# Schematic.net
KiCad netlist of a schematic drawn in Altium Designer
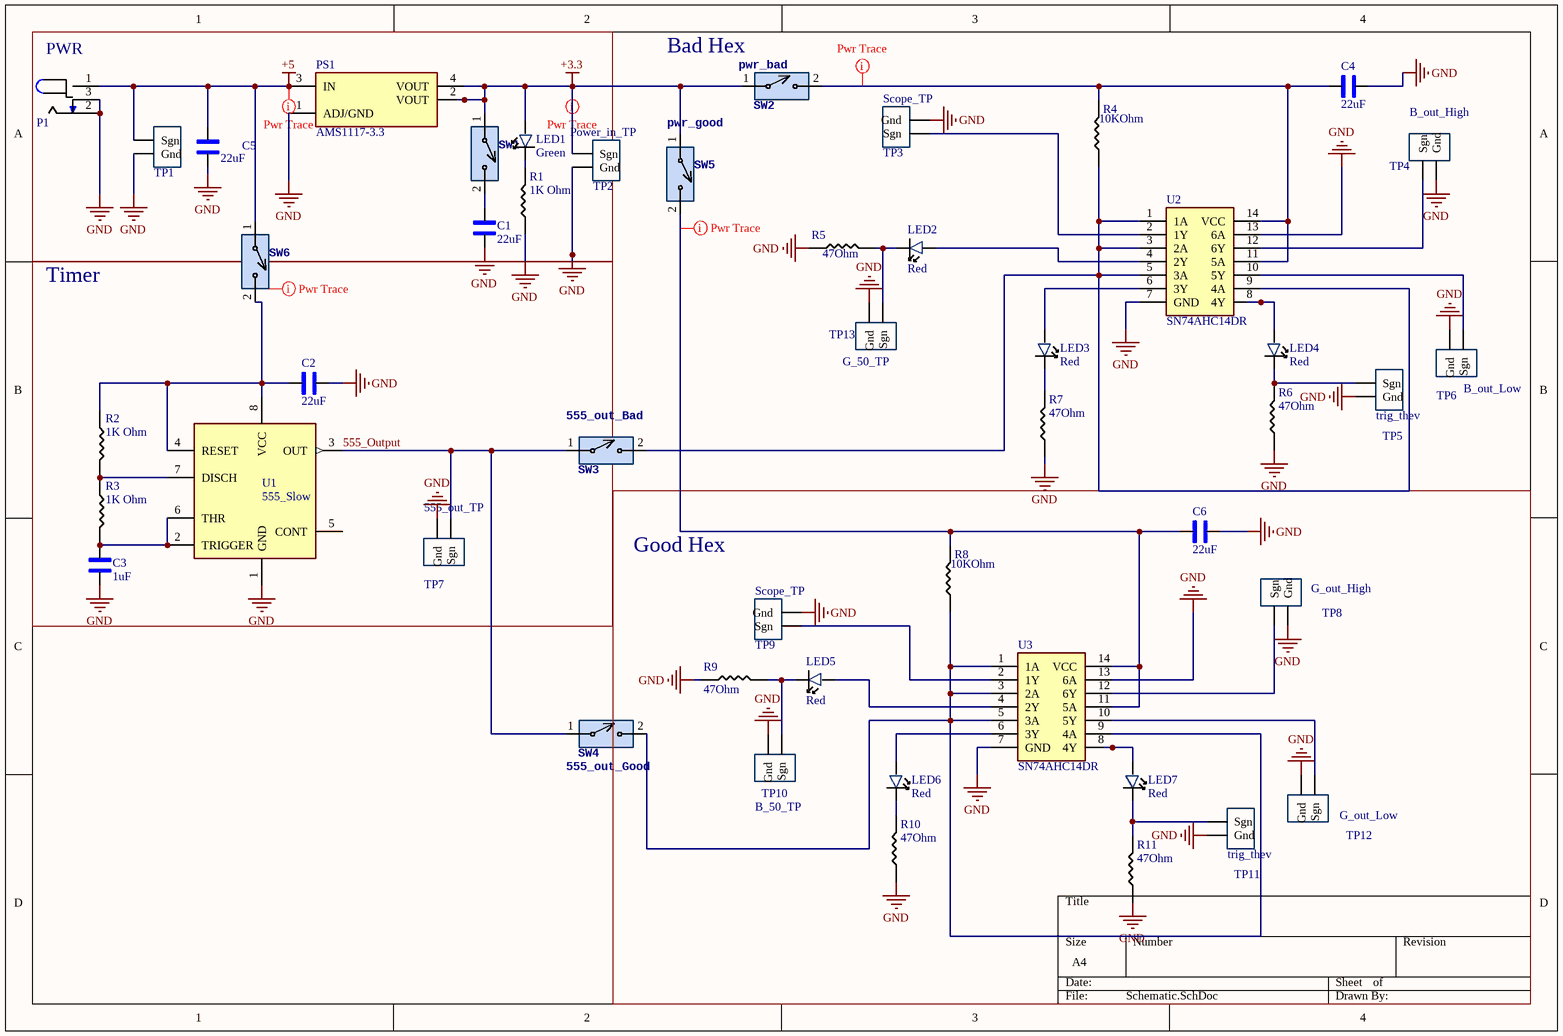
[diagram p0: Schematic.SchDoc]

(export (version "E")
  (design (tool "Eeschema 10.0.6"))
  (components
    (comp (ref "C1")
      (value "22uF")
      (footprint "1206_Passive_Capacitor")
      (description "22uF ±10% 25V X5R 1206 Multilayer Ceramic Capacitors MLCC - SMD/SMT RoHS")
      (fields (field (name "MFR PART #") "CL31A226KAHNNNE") (field (name "LCSC PART#") "C12891"))
      (libsource (lib "ECEN5730Lib_2023_05_DS") (part "C_22uF_1206"))
    )
    (comp (ref "C2")
      (value "22uF")
      (footprint "1206_Passive_Capacitor")
      (description "22uF ±10% 25V X5R 1206 Multilayer Ceramic Capacitors MLCC - SMD/SMT RoHS")
      (fields (field (name "MFR PART #") "CL31A226KAHNNNE") (field (name "LCSC PART#") "C12891"))
      (libsource (lib "ECEN5730Lib_2023_05_DS") (part "C_22uF_1206"))
    )
    (comp (ref "C3")
      (value "1uF")
      (footprint "1206_Passive_Capacitor")
      (description "MULTILAYER CERAMIC CAPACITORS MLCC - SMD/SMT 1UF 50V 1206 ROHS")
      (fields (field (name "MFR PART #") "CL31B105KBHNNNE") (field (name "LCSC PART#") "C1848"))
      (libsource (lib "ECEN5730Lib_2023_05_DS") (part "C_1uF_1206"))
    )
    (comp (ref "C4")
      (value "22uF")
      (footprint "1206_Passive_Capacitor")
      (description "22uF ±10% 25V X5R 1206 Multilayer Ceramic Capacitors MLCC - SMD/SMT RoHS")
      (fields (field (name "MFR PART #") "CL31A226KAHNNNE") (field (name "LCSC PART#") "C12891"))
      (libsource (lib "ECEN5730Lib_2023_05_DS") (part "C_22uF_1206"))
    )
    (comp (ref "C5")
      (value "22uF")
      (footprint "1206_Passive_Capacitor")
      (description "22uF ±10% 25V X5R 1206 Multilayer Ceramic Capacitors MLCC - SMD/SMT RoHS")
      (fields (field (name "MFR PART #") "CL31A226KAHNNNE") (field (name "LCSC PART#") "C12891"))
      (libsource (lib "ECEN5730Lib_2023_05_DS") (part "C_22uF_1206"))
    )
    (comp (ref "C6")
      (value "22uF")
      (footprint "1206_Passive_Capacitor")
      (description "22uF ±10% 25V X5R 1206 Multilayer Ceramic Capacitors MLCC - SMD/SMT RoHS")
      (fields (field (name "MFR PART #") "CL31A226KAHNNNE") (field (name "LCSC PART#") "C12891"))
      (libsource (lib "ECEN5730Lib_2023_05_DS") (part "C_22uF_1206"))
    )
    (comp (ref "LED1")
      (value "Green")
      (footprint "LED_1206")
      (description "Green 513~528nm 1206 Light Emitting Diodes (LED) RoHS")
      (fields (field (name "MFR PART #") "SZYY1206G") (field (name "LCSC PART#") "C434439"))
      (libsource (lib "ECEN5730Lib_2023_05_DS") (part "LED_GREEN_1206"))
    )
    (comp (ref "LED2")
      (value "Red")
      (footprint "LED_1206")
      (description "Red 621~631nm 1206 Light Emitting Diodes (LED) RoHS")
      (fields (field (name "MFR PART #") "15-21/R6C-FQ1R1B/2T") (field (name "LCSC PART#") "C93133"))
      (libsource (lib "ECEN5730Lib_2023_05_DS") (part "LED_RED_1206"))
    )
    (comp (ref "LED3")
      (value "Red")
      (footprint "LED_1206")
      (description "Red 621~631nm 1206 Light Emitting Diodes (LED) RoHS")
      (fields (field (name "MFR PART #") "15-21/R6C-FQ1R1B/2T") (field (name "LCSC PART#") "C93133"))
      (libsource (lib "ECEN5730Lib_2023_05_DS") (part "LED_RED_1206"))
    )
    (comp (ref "LED4")
      (value "Red")
      (footprint "LED_1206")
      (description "Red 621~631nm 1206 Light Emitting Diodes (LED) RoHS")
      (fields (field (name "MFR PART #") "15-21/R6C-FQ1R1B/2T") (field (name "LCSC PART#") "C93133"))
      (libsource (lib "ECEN5730Lib_2023_05_DS") (part "LED_RED_1206"))
    )
    (comp (ref "LED5")
      (value "Red")
      (footprint "LED_1206")
      (description "Red 621~631nm 1206 Light Emitting Diodes (LED) RoHS")
      (fields (field (name "MFR PART #") "15-21/R6C-FQ1R1B/2T") (field (name "LCSC PART#") "C93133"))
      (libsource (lib "ECEN5730Lib_2023_05_DS") (part "LED_RED_1206"))
    )
    (comp (ref "LED6")
      (value "Red")
      (footprint "LED_1206")
      (description "Red 621~631nm 1206 Light Emitting Diodes (LED) RoHS")
      (fields (field (name "MFR PART #") "15-21/R6C-FQ1R1B/2T") (field (name "LCSC PART#") "C93133"))
      (libsource (lib "ECEN5730Lib_2023_05_DS") (part "LED_RED_1206"))
    )
    (comp (ref "LED7")
      (value "Red")
      (footprint "LED_1206")
      (description "Red 621~631nm 1206 Light Emitting Diodes (LED) RoHS")
      (fields (field (name "MFR PART #") "15-21/R6C-FQ1R1B/2T") (field (name "LCSC PART#") "C93133"))
      (libsource (lib "ECEN5730Lib_2023_05_DS") (part "LED_RED_1206"))
    )
    (comp (ref "P1")
      (value "Power Jack")
      (footprint "Power_Jack")
      (description "Power Barrel Connector Jack 2.10mm ID (0.083\"), 5.50mm OD (0.217\") Through Hole, Right Angle")
      (fields (field (name "MFR PART #") "PJ-102A") (field (name "LCSC PART#") "C136744"))
      (libsource (lib "ECEN5730Lib_2023_05_DS") (part "P_Power Jack"))
    )
    (comp (ref "PS1")
      (value "AMS1117-3.3")
      (footprint "LDO")
      (description "LOW DROPOUT REGULATORS(LDO) POSITIVE FIXED 1.3V @ 800MA 15V 3.3V 1A SOT-223 ROHS")
      (fields (field (name "LCSC PART#") "C6186"))
      (libsource (lib "ECEN5730Lib_2023_05_DS") (part "PS_AMS_LDO_3v3"))
    )
    (comp (ref "R1")
      (value "1K Ohm")
      (footprint "1206_Passive_Resitor")
      (description "CHIP RESISTOR - SURFACE MOUNT 1KOHMS ±1% 1/4W 1206 ROHS")
      (fields (field (name "MFR PART #") "RNCP1206FTD1K00CT") (field (name "LCSC PART#") "C4410"))
      (libsource (lib "ECEN5730Lib_2023_05_DS") (part "R_1K_1206"))
    )
    (comp (ref "R2")
      (value "1K Ohm")
      (footprint "1206_Passive_Resitor")
      (description "CHIP RESISTOR - SURFACE MOUNT 1KOHMS ±1% 1/4W 1206 ROHS")
      (fields (field (name "MFR PART #") "RNCP1206FTD1K00CT") (field (name "LCSC PART#") "C4410"))
      (libsource (lib "ECEN5730Lib_2023_05_DS") (part "R_1K_1206"))
    )
    (comp (ref "R3")
      (value "1K Ohm")
      (footprint "1206_Passive_Resitor")
      (description "CHIP RESISTOR - SURFACE MOUNT 1KOHMS ±1% 1/4W 1206 ROHS")
      (fields (field (name "MFR PART #") "RNCP1206FTD1K00CT") (field (name "LCSC PART#") "C4410"))
      (libsource (lib "ECEN5730Lib_2023_05_DS") (part "R_1K_1206"))
    )
    (comp (ref "R4")
      (value "10KOhm")
      (footprint "1206_Passive_Resitor")
      (description "10 kOhms ±5% 0.25W, 1/4W Chip Resistor 1206 (3216 Metric) Automotive AEC-Q200 Thick Film")
      (fields (field (name "MFR PART #") "RMCF1206FT10K0") (field (name "LCSC PART#") "C17902"))
      (libsource (lib "ECEN5730Lib_2023_05_DS") (part "R_10KOhm_1206"))
    )
    (comp (ref "R5")
      (value "47Ohm")
      (footprint "1206_Passive_Resitor")
      (description "47Ω ±5% 0.25W ±200ppm/℃ 1206 Chip Resistor - Surface Mount RoHS")
      (fields (field (name "MFR PART #") "1206W4J0470T5E") (field (name "LCSC PART#") "C25384"))
      (libsource (lib "ECEN5730Lib_2023_05_DS") (part "R_47Ohm_1206"))
    )
    (comp (ref "R6")
      (value "47Ohm")
      (footprint "1206_Passive_Resitor")
      (description "47Ω ±5% 0.25W ±200ppm/℃ 1206 Chip Resistor - Surface Mount RoHS")
      (fields (field (name "MFR PART #") "1206W4J0470T5E") (field (name "LCSC PART#") "C25384"))
      (libsource (lib "ECEN5730Lib_2023_05_DS") (part "R_47Ohm_1206"))
    )
    (comp (ref "R7")
      (value "47Ohm")
      (footprint "1206_Passive_Resitor")
      (description "47Ω ±5% 0.25W ±200ppm/℃ 1206 Chip Resistor - Surface Mount RoHS")
      (fields (field (name "MFR PART #") "1206W4J0470T5E") (field (name "LCSC PART#") "C25384"))
      (libsource (lib "ECEN5730Lib_2023_05_DS") (part "R_47Ohm_1206"))
    )
    (comp (ref "R8")
      (value "10KOhm")
      (footprint "1206_Passive_Resitor")
      (description "10 kOhms ±5% 0.25W, 1/4W Chip Resistor 1206 (3216 Metric) Automotive AEC-Q200 Thick Film")
      (fields (field (name "MFR PART #") "RMCF1206FT10K0") (field (name "LCSC PART#") "C17902"))
      (libsource (lib "ECEN5730Lib_2023_05_DS") (part "R_10KOhm_1206"))
    )
    (comp (ref "R9")
      (value "47Ohm")
      (footprint "1206_Passive_Resitor")
      (description "47Ω ±5% 0.25W ±200ppm/℃ 1206 Chip Resistor - Surface Mount RoHS")
      (fields (field (name "MFR PART #") "1206W4J0470T5E") (field (name "LCSC PART#") "C25384"))
      (libsource (lib "ECEN5730Lib_2023_05_DS") (part "R_47Ohm_1206"))
    )
    (comp (ref "R10")
      (value "47Ohm")
      (footprint "1206_Passive_Resitor")
      (description "47Ω ±5% 0.25W ±200ppm/℃ 1206 Chip Resistor - Surface Mount RoHS")
      (fields (field (name "MFR PART #") "1206W4J0470T5E") (field (name "LCSC PART#") "C25384"))
      (libsource (lib "ECEN5730Lib_2023_05_DS") (part "R_47Ohm_1206"))
    )
    (comp (ref "R11")
      (value "47Ohm")
      (footprint "1206_Passive_Resitor")
      (description "47Ω ±5% 0.25W ±200ppm/℃ 1206 Chip Resistor - Surface Mount RoHS")
      (fields (field (name "MFR PART #") "1206W4J0470T5E") (field (name "LCSC PART#") "C25384"))
      (libsource (lib "ECEN5730Lib_2023_05_DS") (part "R_47Ohm_1206"))
    )
    (comp (ref "SW1")
      (value "SW_2Pin_100mil_Switch")
      (footprint "2Pin-Header-Conn")
      (description "2Pin Header")
      (fields (field (name "LCSC PART#") "C124375"))
      (libsource (lib "ECEN5730Lib_2023_05_DS") (part "SW_2Pin_100mil_Switch"))
    )
    (comp (ref "SW2")
      (value "pwr_bad")
      (footprint "2Pin-Header-Conn")
      (description "2Pin Header")
      (fields (field (name "LCSC PART#") "C124375"))
      (libsource (lib "") (part "SW_2Pin_100mil_Switch_1"))
    )
    (comp (ref "SW3")
      (value "555_out_Bad")
      (footprint "2Pin-Header-Conn")
      (description "2Pin Header")
      (fields (field (name "LCSC PART#") "C124375"))
      (libsource (lib "") (part "SW_2Pin_100mil_Switch_1"))
    )
    (comp (ref "SW4")
      (value "555_out_Good")
      (footprint "2Pin-Header-Conn")
      (description "2Pin Header")
      (fields (field (name "LCSC PART#") "C124375"))
      (libsource (lib "") (part "SW_2Pin_100mil_Switch_1"))
    )
    (comp (ref "SW5")
      (value "pwr_good")
      (footprint "2Pin-Header-Conn")
      (description "2Pin Header")
      (fields (field (name "LCSC PART#") "C124375"))
      (libsource (lib "ECEN5730Lib_2023_05_DS") (part "SW_2Pin_100mil_Switch"))
    )
    (comp (ref "SW6")
      (value "Pwr_555_SW")
      (footprint "2Pin-Header-Conn")
      (description "2Pin Header")
      (fields (field (name "LCSC PART#") "C124375"))
      (libsource (lib "ECEN5730Lib_2023_05_DS") (part "SW_2Pin_100mil_Switch"))
    )
    (comp (ref "TP1")
      (value "Power_in_TP")
      (footprint "TP10x_Probe")
      (description "Test Point 300 mil centers")
      (libsource (lib "ECEN5730Lib_2023_05_DS") (part "TP_10x_Probe"))
    )
    (comp (ref "TP2")
      (value "Power_in_TP")
      (footprint "TP10x_Probe")
      (description "Test Point 300 mil centers")
      (libsource (lib "ECEN5730Lib_2023_05_DS") (part "TP_10x_Probe"))
    )
    (comp (ref "TP3")
      (value "Scope_TP")
      (footprint "TP10x_Probe")
      (description "Test Point 300 mil centers")
      (libsource (lib "") (part "TP_10x_Probe_2"))
    )
    (comp (ref "TP4")
      (value "B_out_High")
      (footprint "TP10x_Probe")
      (description "Test Point 300 mil centers")
      (libsource (lib "") (part "TP_10x_Probe_3"))
    )
    (comp (ref "TP5")
      (value "trig_thev")
      (footprint "TP10x_Probe")
      (description "Test Point 300 mil centers")
      (libsource (lib "ECEN5730Lib_2023_05_DS") (part "TP_10x_Probe"))
    )
    (comp (ref "TP6")
      (value "B_out_Low")
      (footprint "TP10x_Probe")
      (description "Test Point 300 mil centers")
      (libsource (lib "") (part "TP_10x_Probe_1"))
    )
    (comp (ref "TP7")
      (value "555_out_TP")
      (footprint "TP10x_Probe")
      (description "Test Point 300 mil centers")
      (libsource (lib "") (part "TP_10x_Probe_1"))
    )
    (comp (ref "TP8")
      (value "G_out_High")
      (footprint "TP10x_Probe")
      (description "Test Point 300 mil centers")
      (libsource (lib "") (part "TP_10x_Probe_3"))
    )
    (comp (ref "TP9")
      (value "Scope_TP")
      (footprint "TP10x_Probe")
      (description "Test Point 300 mil centers")
      (libsource (lib "") (part "TP_10x_Probe_2"))
    )
    (comp (ref "TP10")
      (value "B_50_TP")
      (footprint "TP10x_Probe")
      (description "Test Point 300 mil centers")
      (libsource (lib "") (part "TP_10x_Probe_1"))
    )
    (comp (ref "TP11")
      (value "trig_thev")
      (footprint "TP10x_Probe")
      (description "Test Point 300 mil centers")
      (libsource (lib "ECEN5730Lib_2023_05_DS") (part "TP_10x_Probe"))
    )
    (comp (ref "TP12")
      (value "G_out_Low")
      (footprint "TP10x_Probe")
      (description "Test Point 300 mil centers")
      (libsource (lib "") (part "TP_10x_Probe_1"))
    )
    (comp (ref "TP13")
      (value "G_50_TP")
      (footprint "TP10x_Probe")
      (description "Test Point 300 mil centers")
      (libsource (lib "") (part "TP_10x_Probe_1"))
    )
    (comp (ref "U1")
      (value "555_Slow")
      (footprint "TS555IDTTR")
      (description "555 Timer SOIC-8_150MIL ROHS 150ns Rise Time")
      (fields (field (name "MFR PART #") "NE555DR") (field (name "LCSC PART#") "C7593"))
      (libsource (lib "ECEN5730Lib_2023_05_DS") (part "U_555_Slow"))
    )
    (comp (ref "U2")
      (value "SN74AHC14DR")
      (footprint "HEX_74AC14")
      (description "Inverter IC 6 Channel Schmitt Trigger 14-SOIC")
      (fields (field (name "LCSC PART#") "C6942"))
      (libsource (lib "ECEN5730Lib_2023_05_DS") (part "U_74AHC14"))
    )
    (comp (ref "U3")
      (value "SN74AHC14DR")
      (footprint "HEX_74AC14")
      (description "Inverter IC 6 Channel Schmitt Trigger 14-SOIC")
      (fields (field (name "LCSC PART#") "C6942"))
      (libsource (lib "ECEN5730Lib_2023_05_DS") (part "U_74AHC14"))
    )
  )
  (nets
    (net (code "1") (name "+3.3") (class "Default")
      (node (ref "LED1") (pin "1") (pinfunction "1_1") (pintype "passive"))
      (node (ref "PS1") (pin "2") (pinfunction "VOUT_2") (pintype "power_in"))
      (node (ref "PS1") (pin "4") (pinfunction "VOUT_4") (pintype "power_in"))
      (node (ref "SW1") (pin "1") (pinfunction "1_1") (pintype "passive"))
      (node (ref "SW2") (pin "1") (pinfunction "1_1") (pintype "passive"))
      (node (ref "SW5") (pin "1") (pinfunction "1_1") (pintype "passive"))
      (node (ref "TP2") (pin "1") (pinfunction "Sgn_1") (pintype "passive"))
    )
    (net (code "2") (name "+5") (class "Default")
      (node (ref "C5") (pin "2") (pinfunction "2_2") (pintype "passive"))
      (node (ref "P1") (pin "1") (pinfunction "1_1") (pintype "power_in"))
      (node (ref "PS1") (pin "3") (pinfunction "IN_3") (pintype "power_in"))
      (node (ref "SW6") (pin "1") (pinfunction "1_1") (pintype "passive"))
      (node (ref "TP1") (pin "1") (pinfunction "Sgn_1") (pintype "passive"))
    )
    (net (code "3") (name "/555_Output") (class "Default")
      (node (ref "SW3") (pin "1") (pinfunction "1_1") (pintype "passive"))
      (node (ref "SW4") (pin "1") (pinfunction "1_1") (pintype "passive"))
      (node (ref "TP7") (pin "1") (pinfunction "Sgn_1") (pintype "passive"))
      (node (ref "U1") (pin "3") (pinfunction "OUT_3") (pintype "output"))
    )
    (net (code "4") (name "GND") (class "Default")
      (node (ref "C1") (pin "1") (pinfunction "1_1") (pintype "passive"))
      (node (ref "C2") (pin "1") (pinfunction "1_1") (pintype "passive"))
      (node (ref "C3") (pin "2") (pinfunction "2_2") (pintype "passive"))
      (node (ref "C4") (pin "1") (pinfunction "1_1") (pintype "passive"))
      (node (ref "C5") (pin "1") (pinfunction "1_1") (pintype "passive"))
      (node (ref "C6") (pin "1") (pinfunction "1_1") (pintype "passive"))
      (node (ref "P1") (pin "2") (pinfunction "2_2") (pintype "power_in"))
      (node (ref "P1") (pin "3") (pinfunction "3_3") (pintype "power_in"))
      (node (ref "PS1") (pin "1") (pinfunction "ADJ/GND_1") (pintype "passive"))
      (node (ref "R1") (pin "1") (pinfunction "1_1") (pintype "passive"))
      (node (ref "R10") (pin "1") (pinfunction "1_1") (pintype "passive"))
      (node (ref "R11") (pin "1") (pinfunction "1_1") (pintype "passive"))
      (node (ref "R5") (pin "1") (pinfunction "1_1") (pintype "passive"))
      (node (ref "R6") (pin "1") (pinfunction "1_1") (pintype "passive"))
      (node (ref "R7") (pin "1") (pinfunction "1_1") (pintype "passive"))
      (node (ref "R9") (pin "1") (pinfunction "1_1") (pintype "passive"))
      (node (ref "TP1") (pin "2") (pinfunction "Gnd_2") (pintype "passive"))
      (node (ref "TP10") (pin "2") (pinfunction "Gnd_2") (pintype "passive"))
      (node (ref "TP11") (pin "2") (pinfunction "Gnd_2") (pintype "passive"))
      (node (ref "TP12") (pin "2") (pinfunction "Gnd_2") (pintype "passive"))
      (node (ref "TP13") (pin "2") (pinfunction "Gnd_2") (pintype "passive"))
      (node (ref "TP2") (pin "2") (pinfunction "Gnd_2") (pintype "passive"))
      (node (ref "TP3") (pin "2") (pinfunction "Gnd_2") (pintype "passive"))
      (node (ref "TP4") (pin "2") (pinfunction "Gnd_2") (pintype "passive"))
      (node (ref "TP5") (pin "2") (pinfunction "Gnd_2") (pintype "passive"))
      (node (ref "TP6") (pin "2") (pinfunction "Gnd_2") (pintype "passive"))
      (node (ref "TP7") (pin "2") (pinfunction "Gnd_2") (pintype "passive"))
      (node (ref "TP8") (pin "2") (pinfunction "Gnd_2") (pintype "passive"))
      (node (ref "TP9") (pin "2") (pinfunction "Gnd_2") (pintype "passive"))
      (node (ref "U1") (pin "1") (pinfunction "GND_1") (pintype "power_in"))
      (node (ref "U2") (pin "13") (pinfunction "6A_13") (pintype "passive"))
      (node (ref "U2") (pin "7") (pinfunction "GND_7") (pintype "passive"))
      (node (ref "U3") (pin "13") (pinfunction "6A_13") (pintype "passive"))
      (node (ref "U3") (pin "7") (pinfunction "GND_7") (pintype "passive"))
    )
    (net (code "5") (name "Net-(C1-Pad2)") (class "Default")
      (node (ref "C1") (pin "2") (pinfunction "2_2") (pintype "passive"))
      (node (ref "SW1") (pin "2") (pinfunction "2_2") (pintype "passive"))
    )
    (net (code "6") (name "Net-(LED1-Pad2)") (class "Default")
      (node (ref "LED1") (pin "2") (pinfunction "2_2") (pintype "passive"))
      (node (ref "R1") (pin "2") (pinfunction "2_2") (pintype "passive"))
    )
    (net (code "7") (name "Net-(LED3-Pad2)") (class "Default")
      (node (ref "LED3") (pin "2") (pinfunction "2_2") (pintype "passive"))
      (node (ref "R7") (pin "2") (pinfunction "2_2") (pintype "passive"))
    )
    (net (code "8") (name "Net-(LED6-Pad2)") (class "Default")
      (node (ref "LED6") (pin "2") (pinfunction "2_2") (pintype "passive"))
      (node (ref "R10") (pin "2") (pinfunction "2_2") (pintype "passive"))
    )
    (net (code "9") (name "Net-(TP3-Sgn)") (class "Default")
      (node (ref "TP3") (pin "1") (pinfunction "Sgn_1") (pintype "passive"))
      (node (ref "U2") (pin "2") (pinfunction "1Y_2") (pintype "passive"))
    )
    (net (code "10") (name "Net-(TP4-Sgn)") (class "Default")
      (node (ref "TP4") (pin "1") (pinfunction "Sgn_1") (pintype "passive"))
      (node (ref "U2") (pin "12") (pinfunction "6Y_12") (pintype "passive"))
    )
    (net (code "11") (name "Net-(TP5-Sgn)") (class "Default")
      (node (ref "LED4") (pin "2") (pinfunction "2_2") (pintype "passive"))
      (node (ref "R6") (pin "2") (pinfunction "2_2") (pintype "passive"))
      (node (ref "TP5") (pin "1") (pinfunction "Sgn_1") (pintype "passive"))
    )
    (net (code "12") (name "Net-(TP6-Sgn)") (class "Default")
      (node (ref "TP6") (pin "1") (pinfunction "Sgn_1") (pintype "passive"))
      (node (ref "U2") (pin "10") (pinfunction "5Y_10") (pintype "passive"))
    )
    (net (code "13") (name "Net-(TP8-Sgn)") (class "Default")
      (node (ref "TP8") (pin "1") (pinfunction "Sgn_1") (pintype "passive"))
      (node (ref "U3") (pin "12") (pinfunction "6Y_12") (pintype "passive"))
    )
    (net (code "14") (name "Net-(TP9-Sgn)") (class "Default")
      (node (ref "TP9") (pin "1") (pinfunction "Sgn_1") (pintype "passive"))
      (node (ref "U3") (pin "2") (pinfunction "1Y_2") (pintype "passive"))
    )
    (net (code "15") (name "Net-(TP10-Sgn)") (class "Default")
      (node (ref "LED5") (pin "2") (pinfunction "2_2") (pintype "passive"))
      (node (ref "R9") (pin "2") (pinfunction "2_2") (pintype "passive"))
      (node (ref "TP10") (pin "1") (pinfunction "Sgn_1") (pintype "passive"))
    )
    (net (code "16") (name "Net-(TP11-Sgn)") (class "Default")
      (node (ref "LED7") (pin "2") (pinfunction "2_2") (pintype "passive"))
      (node (ref "R11") (pin "2") (pinfunction "2_2") (pintype "passive"))
      (node (ref "TP11") (pin "1") (pinfunction "Sgn_1") (pintype "passive"))
    )
    (net (code "17") (name "Net-(TP12-Sgn)") (class "Default")
      (node (ref "TP12") (pin "1") (pinfunction "Sgn_1") (pintype "passive"))
      (node (ref "U3") (pin "10") (pinfunction "5Y_10") (pintype "passive"))
    )
    (net (code "18") (name "Net-(TP13-Sgn)") (class "Default")
      (node (ref "LED2") (pin "2") (pinfunction "2_2") (pintype "passive"))
      (node (ref "R5") (pin "2") (pinfunction "2_2") (pintype "passive"))
      (node (ref "TP13") (pin "1") (pinfunction "Sgn_1") (pintype "passive"))
    )
    (net (code "19") (name "Net-(U1-DISCH)") (class "Default")
      (node (ref "R2") (pin "2") (pinfunction "2_2") (pintype "passive"))
      (node (ref "R3") (pin "1") (pinfunction "1_1") (pintype "passive"))
      (node (ref "U1") (pin "7") (pinfunction "DISCH_7") (pintype "passive"))
    )
    (net (code "20") (name "Net-(U1-RESET)") (class "Default")
      (node (ref "C2") (pin "2") (pinfunction "2_2") (pintype "passive"))
      (node (ref "R2") (pin "1") (pinfunction "1_1") (pintype "passive"))
      (node (ref "SW6") (pin "2") (pinfunction "2_2") (pintype "passive"))
      (node (ref "U1") (pin "4") (pinfunction "RESET_4") (pintype "passive"))
      (node (ref "U1") (pin "8") (pinfunction "VCC_8") (pintype "power_in"))
    )
    (net (code "21") (name "Net-(U1-THR)") (class "Default")
      (node (ref "C3") (pin "1") (pinfunction "1_1") (pintype "passive"))
      (node (ref "R3") (pin "2") (pinfunction "2_2") (pintype "passive"))
      (node (ref "U1") (pin "2") (pinfunction "TRIGGER_2") (pintype "passive"))
      (node (ref "U1") (pin "6") (pinfunction "THR_6") (pintype "passive"))
    )
    (net (code "22") (name "Net-(U2-1A)") (class "Default")
      (node (ref "R4") (pin "1") (pinfunction "1_1") (pintype "passive"))
      (node (ref "SW3") (pin "2") (pinfunction "2_2") (pintype "passive"))
      (node (ref "U2") (pin "1") (pinfunction "1A_1") (pintype "passive"))
      (node (ref "U2") (pin "3") (pinfunction "2A_3") (pintype "passive"))
      (node (ref "U2") (pin "5") (pinfunction "3A_5") (pintype "passive"))
      (node (ref "U2") (pin "9") (pinfunction "4A_9") (pintype "passive"))
    )
    (net (code "23") (name "Net-(U2-2Y)") (class "Default")
      (node (ref "LED2") (pin "1") (pinfunction "1_1") (pintype "passive"))
      (node (ref "U2") (pin "4") (pinfunction "2Y_4") (pintype "passive"))
    )
    (net (code "24") (name "Net-(U2-3Y)") (class "Default")
      (node (ref "LED3") (pin "1") (pinfunction "1_1") (pintype "passive"))
      (node (ref "U2") (pin "6") (pinfunction "3Y_6") (pintype "passive"))
    )
    (net (code "25") (name "Net-(U2-4Y)") (class "Default")
      (node (ref "LED4") (pin "1") (pinfunction "1_1") (pintype "passive"))
      (node (ref "U2") (pin "8") (pinfunction "4Y_8") (pintype "passive"))
    )
    (net (code "26") (name "Net-(U2-5A)") (class "Default")
      (node (ref "C4") (pin "2") (pinfunction "2_2") (pintype "passive"))
      (node (ref "R4") (pin "2") (pinfunction "2_2") (pintype "passive"))
      (node (ref "SW2") (pin "2") (pinfunction "2_2") (pintype "passive"))
      (node (ref "U2") (pin "11") (pinfunction "5A_11") (pintype "passive"))
      (node (ref "U2") (pin "14") (pinfunction "VCC_14") (pintype "passive"))
    )
    (net (code "27") (name "Net-(U3-1A)") (class "Default")
      (node (ref "R8") (pin "1") (pinfunction "1_1") (pintype "passive"))
      (node (ref "SW4") (pin "2") (pinfunction "2_2") (pintype "passive"))
      (node (ref "U3") (pin "1") (pinfunction "1A_1") (pintype "passive"))
      (node (ref "U3") (pin "3") (pinfunction "2A_3") (pintype "passive"))
      (node (ref "U3") (pin "5") (pinfunction "3A_5") (pintype "passive"))
      (node (ref "U3") (pin "9") (pinfunction "4A_9") (pintype "passive"))
    )
    (net (code "28") (name "Net-(U3-2Y)") (class "Default")
      (node (ref "LED5") (pin "1") (pinfunction "1_1") (pintype "passive"))
      (node (ref "U3") (pin "4") (pinfunction "2Y_4") (pintype "passive"))
    )
    (net (code "29") (name "Net-(U3-3Y)") (class "Default")
      (node (ref "LED6") (pin "1") (pinfunction "1_1") (pintype "passive"))
      (node (ref "U3") (pin "6") (pinfunction "3Y_6") (pintype "passive"))
    )
    (net (code "30") (name "Net-(U3-4Y)") (class "Default")
      (node (ref "LED7") (pin "1") (pinfunction "1_1") (pintype "passive"))
      (node (ref "U3") (pin "8") (pinfunction "4Y_8") (pintype "passive"))
    )
    (net (code "31") (name "Net-(U3-5A)") (class "Default")
      (node (ref "C6") (pin "2") (pinfunction "2_2") (pintype "passive"))
      (node (ref "R8") (pin "2") (pinfunction "2_2") (pintype "passive"))
      (node (ref "SW5") (pin "2") (pinfunction "2_2") (pintype "passive"))
      (node (ref "U3") (pin "11") (pinfunction "5A_11") (pintype "passive"))
      (node (ref "U3") (pin "14") (pinfunction "VCC_14") (pintype "passive"))
    )
    (net (code "32") (name "unconnected-(U1-CONT-Pad5)") (class "Default")
      (node (ref "U1") (pin "5") (pinfunction "CONT_5") (pintype "passive"))
    )
  )
)
